# REGENIX_Battery_Protection.net
KiCad netlist of a schematic drawn in Altium Designer
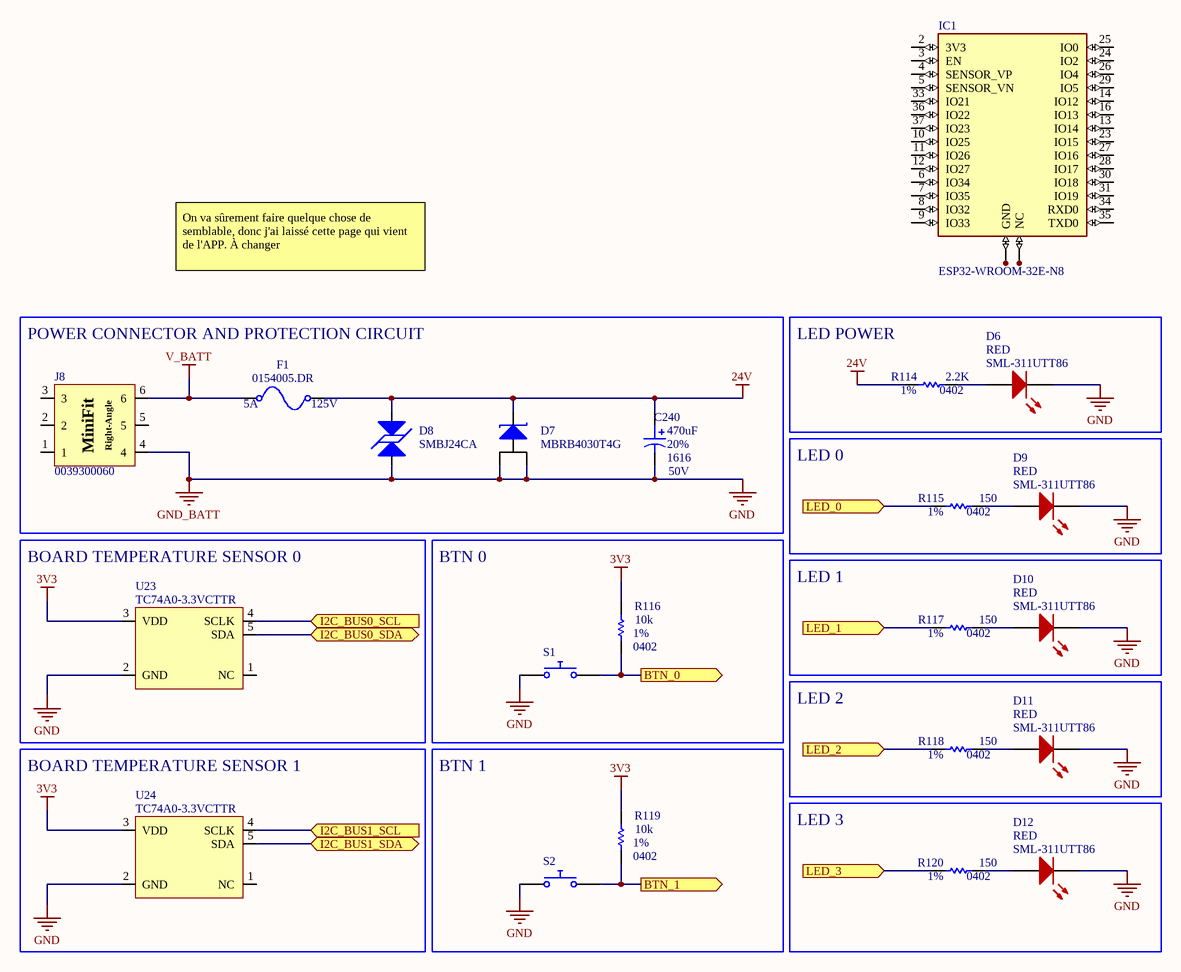
[diagram p0: REGENIX_Battery_Protection.SchDoc]

(export (version "E")
  (design (tool "Eeschema 10.0.6"))
  (components
    (comp (ref "C240")
      (value "470uF")
      (footprint "CAP_ALU_1616_vishay")
      (description "CAP - ALU 470uF 20% 50V - 1616")
      (fields
        (field (name "MFG") "Vishay Dale")
        (field (name "MFG PART NUMBER") "MAL214699108E3")
        (field (name "VOLTAGE") "50V")
        (field (name "PACKAGE") "1616")
        (field (name "PRECISION") "20%")
        (field (name "CREATEDBY") "Jonathan Bouchard")
      )
      (libsource (lib "S7CAS_LIB2023") (part "CAP_ALU_MAL214699108E3"))
    )
    (comp (ref "D6")
      (value "SML-311UTT86")
      (footprint "LED_0603")
      (description "LED - 620nM RED 2mA - 0603")
      (fields
        (field (name "VOLTAGE") "1.8V")
        (field (name "MFG") "ROHM Semiconductor")
        (field (name "ALTIUM_VALUE") "RED")
        (field (name "CREATEDBY") "Jonathan Bouchard")
      )
      (libsource (lib "S7CAS_LIB2023") (part "LED_SML-311UTT86"))
    )
    (comp (ref "D7")
      (value "MBRB4030T4G")
      (footprint "DIO_SCHOTTKY_MBRB4030T4G")
      (description "DIO - 30V MAX 40 A - TO-263-3")
      (fields
        (field (name "CREATEDBY/DATE") "Arnaud Samson - 06/07/18")
        (field (name "VERIFIEDBY") "Jonathan Bouchard 2018-07-12")
      )
      (libsource (lib "S7CAS_LIB2023") (part "DIO_SCHOTTKY_MBRB4030T4G"))
    )
    (comp (ref "D8")
      (value "SMBJ24CA")
      (footprint "TVS_PWR_SMBJ36CA")
      (description "TVS - 24V 26.7V 600W - DO214AA")
      (fields
        (field (name "CREATEDBY/DATE") "Arnaud Samson - 06/07/18")
        (field (name "VERIFIEDBY") "Jonathan Bouchard - 2018-07-13")
      )
      (libsource (lib "S7CAS_LIB2023") (part "TVS_PWR_SMBJ24CA"))
    )
    (comp (ref "D9")
      (value "SML-311UTT86")
      (footprint "LED_0603")
      (description "LED - 620nM RED 2mA - 0603")
      (fields
        (field (name "VOLTAGE") "1.8V")
        (field (name "MFG") "ROHM Semiconductor")
        (field (name "ALTIUM_VALUE") "RED")
        (field (name "CREATEDBY") "Jonathan Bouchard")
      )
      (libsource (lib "S7CAS_LIB2023") (part "LED_SML-311UTT86"))
    )
    (comp (ref "D10")
      (value "SML-311UTT86")
      (footprint "LED_0603")
      (description "LED - 620nM RED 2mA - 0603")
      (fields
        (field (name "VOLTAGE") "1.8V")
        (field (name "MFG") "ROHM Semiconductor")
        (field (name "ALTIUM_VALUE") "RED")
        (field (name "CREATEDBY") "Jonathan Bouchard")
      )
      (libsource (lib "S7CAS_LIB2023") (part "LED_SML-311UTT86"))
    )
    (comp (ref "D11")
      (value "SML-311UTT86")
      (footprint "LED_0603")
      (description "LED - 620nM RED 2mA - 0603")
      (fields
        (field (name "VOLTAGE") "1.8V")
        (field (name "MFG") "ROHM Semiconductor")
        (field (name "ALTIUM_VALUE") "RED")
        (field (name "CREATEDBY") "Jonathan Bouchard")
      )
      (libsource (lib "S7CAS_LIB2023") (part "LED_SML-311UTT86"))
    )
    (comp (ref "D12")
      (value "SML-311UTT86")
      (footprint "LED_0603")
      (description "LED - 620nM RED 2mA - 0603")
      (fields
        (field (name "VOLTAGE") "1.8V")
        (field (name "MFG") "ROHM Semiconductor")
        (field (name "ALTIUM_VALUE") "RED")
        (field (name "CREATEDBY") "Jonathan Bouchard")
      )
      (libsource (lib "S7CAS_LIB2023") (part "LED_SML-311UTT86"))
    )
    (comp (ref "F1")
      (value "0154005.DR")
      (footprint "FUS_0154XXX.DR")
      (description "FUS - 5 A 125 VAC/VDC - 2-SMD")
      (fields
        (field (name "VOLTAGE RATING") "125V")
        (field (name "CURRENT RATING") "5A")
        (field (name "CREATEDBY/DATE") "Arnaud Samson - 06/07/18")
        (field (name "VERIFIEDBY") "Jonathan Bouchard 2018-07-16")
      )
      (libsource (lib "S7CAS_LIB2023") (part "FUS_0154005.DR"))
    )
    (comp (ref "IC1")
      (value "ESP32-WROOM-32E-N8")
      (footprint "ESP32WROOM32EN8")
      (fields (field (name "MF") "Espressif Systems"))
      (libsource (lib "ESP32-WROOM-32E-N8") (part "ESP32-WROOM-32E-N8"))
    )
    (comp (ref "J8")
      (value "0039300060")
      (footprint "CON_MINIFIT_0039300060")
      (description "CON - Mini-Fit Through Hole, Right Angle 6 position")
      (fields
        (field (name "CREATEDBY/DATE") "Joel Lemay 2018-06-21")
        (field (name "VERIFIEDBY") "Caroline Paulin - 10 sept 2018")
      )
      (libsource (lib "S7CAS_LIB2023") (part "CON_MINIFIT_0039300060"))
    )
    (comp (ref "R114")
      (value "2.2K")
      (footprint "RES_0402")
      (description "RES - 0402")
      (fields
        (field (name "VOLTAGE") "50V")
        (field (name "POWER") "1/16W")
        (field (name "PACKAGE") "0402")
        (field (name "PRECISION") "1%")
        (field (name "CREATEDBY") "Jonathan Bouchard")
      )
      (libsource (lib "S7CAS_LIB2023") (part "RES - 0402"))
    )
    (comp (ref "R115")
      (value "150")
      (footprint "RES_0402")
      (description "RES - 0402")
      (fields
        (field (name "VOLTAGE") "50V")
        (field (name "POWER") "1/16W")
        (field (name "PACKAGE") "0402")
        (field (name "PRECISION") "1%")
        (field (name "CREATEDBY") "Jonathan Bouchard")
      )
      (libsource (lib "S7CAS_LIB2023") (part "RES - 0402"))
    )
    (comp (ref "R116")
      (value "10k")
      (footprint "RES_0402")
      (description "RES - 0402")
      (fields
        (field (name "VOLTAGE") "50V")
        (field (name "POWER") "1/16W")
        (field (name "PACKAGE") "0402")
        (field (name "PRECISION") "1%")
        (field (name "CREATEDBY") "Jonathan Bouchard")
      )
      (libsource (lib "S7CAS_LIB2023") (part "RES - 0402"))
    )
    (comp (ref "R117")
      (value "150")
      (footprint "RES_0402")
      (description "RES - 0402")
      (fields
        (field (name "VOLTAGE") "50V")
        (field (name "POWER") "1/16W")
        (field (name "PACKAGE") "0402")
        (field (name "PRECISION") "1%")
        (field (name "CREATEDBY") "Jonathan Bouchard")
      )
      (libsource (lib "S7CAS_LIB2023") (part "RES - 0402"))
    )
    (comp (ref "R118")
      (value "150")
      (footprint "RES_0402")
      (description "RES - 0402")
      (fields
        (field (name "VOLTAGE") "50V")
        (field (name "POWER") "1/16W")
        (field (name "PACKAGE") "0402")
        (field (name "PRECISION") "1%")
        (field (name "CREATEDBY") "Jonathan Bouchard")
      )
      (libsource (lib "S7CAS_LIB2023") (part "RES - 0402"))
    )
    (comp (ref "R119")
      (value "10k")
      (footprint "RES_0402")
      (description "RES - 0402")
      (fields
        (field (name "VOLTAGE") "50V")
        (field (name "POWER") "1/16W")
        (field (name "PACKAGE") "0402")
        (field (name "PRECISION") "1%")
        (field (name "CREATEDBY") "Jonathan Bouchard")
      )
      (libsource (lib "S7CAS_LIB2023") (part "RES - 0402"))
    )
    (comp (ref "R120")
      (value "150")
      (footprint "RES_0402")
      (description "RES - 0402")
      (fields
        (field (name "VOLTAGE") "50V")
        (field (name "POWER") "1/16W")
        (field (name "PACKAGE") "0402")
        (field (name "PRECISION") "1%")
        (field (name "CREATEDBY") "Jonathan Bouchard")
      )
      (libsource (lib "S7CAS_LIB2023") (part "RES - 0402"))
    )
    (comp (ref "S1")
      (value "Push Button Normally Opened")
      (libsource (lib "Simulation Generic Components") (part "Push Button NO"))
    )
    (comp (ref "S2")
      (value "Push Button Normally Opened")
      (libsource (lib "Simulation Generic Components") (part "Push Button NO"))
    )
    (comp (ref "U23")
      (value "TC74A0-3.3VCTTR")
      (footprint "SEN_TEMP_TC74A0-3.3VCTTR")
      (description "SENS - TEMPERATURE SENSOR I2C/SMBUS - SOT23-5")
      (fields
        (field (name "VOLTAGE") "2.7 V ~ 5.5 V")
        (field (name "MFG") "Microchip")
        (field (name "CREATEDBY") "Jonathan Bouchard")
      )
      (libsource (lib "S7CAS_LIB2023") (part "SENS_TEMP_TC74A0-3.3VCTTR"))
    )
    (comp (ref "U24")
      (value "TC74A0-3.3VCTTR")
      (footprint "SEN_TEMP_TC74A0-3.3VCTTR")
      (description "SENS - TEMPERATURE SENSOR I2C/SMBUS - SOT23-5")
      (fields
        (field (name "VOLTAGE") "2.7 V ~ 5.5 V")
        (field (name "MFG") "Microchip")
        (field (name "CREATEDBY") "Jonathan Bouchard")
      )
      (libsource (lib "S7CAS_LIB2023") (part "SENS_TEMP_TC74A0-3.3VCTTR"))
    )
  )
  (nets
    (net (code "1") (name "/BTN_0") (class "Default")
      (node (ref "R116") (pin "1") (pinfunction "1_1") (pintype "passive"))
      (node (ref "S1") (pin "2") (pinfunction "2_2") (pintype "passive"))
    )
    (net (code "2") (name "/BTN_1") (class "Default")
      (node (ref "R119") (pin "1") (pinfunction "1_1") (pintype "passive"))
      (node (ref "S2") (pin "2") (pinfunction "2_2") (pintype "passive"))
    )
    (net (code "3") (name "/I2C_BUS0_SCL") (class "Default")
      (node (ref "U23") (pin "4") (pinfunction "SCLK_4") (pintype "passive"))
    )
    (net (code "4") (name "/I2C_BUS0_SDA") (class "Default")
      (node (ref "U23") (pin "5") (pinfunction "SDA_5") (pintype "passive"))
    )
    (net (code "5") (name "/I2C_BUS1_SCL") (class "Default")
      (node (ref "U24") (pin "4") (pinfunction "SCLK_4") (pintype "passive"))
    )
    (net (code "6") (name "/I2C_BUS1_SDA") (class "Default")
      (node (ref "U24") (pin "5") (pinfunction "SDA_5") (pintype "passive"))
    )
    (net (code "7") (name "/LED_0") (class "Default")
      (node (ref "R115") (pin "2") (pinfunction "2_2") (pintype "passive"))
    )
    (net (code "8") (name "/LED_1") (class "Default")
      (node (ref "R117") (pin "2") (pinfunction "2_2") (pintype "passive"))
    )
    (net (code "9") (name "/LED_2") (class "Default")
      (node (ref "R118") (pin "2") (pinfunction "2_2") (pintype "passive"))
    )
    (net (code "10") (name "/LED_3") (class "Default")
      (node (ref "R120") (pin "2") (pinfunction "2_2") (pintype "passive"))
    )
    (net (code "11") (name "3V3") (class "Default")
      (node (ref "R116") (pin "2") (pinfunction "2_2") (pintype "passive"))
      (node (ref "R119") (pin "2") (pinfunction "2_2") (pintype "passive"))
      (node (ref "U23") (pin "3") (pinfunction "VDD_3") (pintype "passive"))
      (node (ref "U24") (pin "3") (pinfunction "VDD_3") (pintype "passive"))
    )
    (net (code "12") (name "24V") (class "Default")
      (node (ref "C240") (pin "1") (pinfunction "1_1") (pintype "passive"))
      (node (ref "D7") (pin "4") (pinfunction "4_4") (pintype "passive"))
      (node (ref "D8") (pin "1") (pinfunction "1_1") (pintype "passive"))
      (node (ref "F1") (pin "2") (pinfunction "2_2") (pintype "passive"))
      (node (ref "R114") (pin "2") (pinfunction "2_2") (pintype "passive"))
    )
    (net (code "13") (name "GND") (class "Default")
      (node (ref "C240") (pin "2") (pinfunction "2_2") (pintype "passive"))
      (node (ref "D10") (pin "K") (pinfunction "K_K") (pintype "passive"))
      (node (ref "D11") (pin "K") (pinfunction "K_K") (pintype "passive"))
      (node (ref "D12") (pin "K") (pinfunction "K_K") (pintype "passive"))
      (node (ref "D6") (pin "K") (pinfunction "K_K") (pintype "passive"))
      (node (ref "D7") (pin "1") (pinfunction "A_1") (pintype "passive"))
      (node (ref "D7") (pin "3") (pinfunction "3_3") (pintype "passive"))
      (node (ref "D8") (pin "2") (pinfunction "2_2") (pintype "passive"))
      (node (ref "D9") (pin "K") (pinfunction "K_K") (pintype "passive"))
      (node (ref "J8") (pin "4") (pinfunction "4_4") (pintype "passive"))
      (node (ref "S1") (pin "1") (pinfunction "1_1") (pintype "passive"))
      (node (ref "S2") (pin "1") (pinfunction "1_1") (pintype "passive"))
      (node (ref "U23") (pin "2") (pinfunction "GND_2") (pintype "passive"))
      (node (ref "U24") (pin "2") (pinfunction "GND_2") (pintype "passive"))
    )
    (net (code "14") (name "Net-(D6-PadA)") (class "Default")
      (node (ref "D6") (pin "A") (pinfunction "A_A") (pintype "passive"))
      (node (ref "R114") (pin "1") (pinfunction "1_1") (pintype "passive"))
    )
    (net (code "15") (name "Net-(D9-PadA)") (class "Default")
      (node (ref "D9") (pin "A") (pinfunction "A_A") (pintype "passive"))
      (node (ref "R115") (pin "1") (pinfunction "1_1") (pintype "passive"))
    )
    (net (code "16") (name "Net-(D10-PadA)") (class "Default")
      (node (ref "D10") (pin "A") (pinfunction "A_A") (pintype "passive"))
      (node (ref "R117") (pin "1") (pinfunction "1_1") (pintype "passive"))
    )
    (net (code "17") (name "Net-(D11-PadA)") (class "Default")
      (node (ref "D11") (pin "A") (pinfunction "A_A") (pintype "passive"))
      (node (ref "R118") (pin "1") (pinfunction "1_1") (pintype "passive"))
    )
    (net (code "18") (name "Net-(D12-PadA)") (class "Default")
      (node (ref "D12") (pin "A") (pinfunction "A_A") (pintype "passive"))
      (node (ref "R120") (pin "1") (pinfunction "1_1") (pintype "passive"))
    )
    (net (code "19") (name "Net-(IC1-GND-Pad1)") (class "Default")
      (node (ref "IC1") (pin "1") (pinfunction "GND_1") (pintype "bidirectional"))
      (node (ref "IC1") (pin "15") (pinfunction "GND_15") (pintype "bidirectional"))
      (node (ref "IC1") (pin "38") (pinfunction "GND_38") (pintype "bidirectional"))
      (node (ref "IC1") (pin "39") (pinfunction "GND_39") (pintype "bidirectional"))
      (node (ref "IC1") (pin "40") (pinfunction "GND_40") (pintype "bidirectional"))
      (node (ref "IC1") (pin "41") (pinfunction "GND_41") (pintype "bidirectional"))
      (node (ref "IC1") (pin "42") (pinfunction "GND_42") (pintype "bidirectional"))
      (node (ref "IC1") (pin "43") (pinfunction "GND_43") (pintype "bidirectional"))
      (node (ref "IC1") (pin "44") (pinfunction "GND_44") (pintype "bidirectional"))
      (node (ref "IC1") (pin "45") (pinfunction "GND_45") (pintype "bidirectional"))
      (node (ref "IC1") (pin "46") (pinfunction "GND_46") (pintype "bidirectional"))
      (node (ref "IC1") (pin "47") (pinfunction "GND_47") (pintype "bidirectional"))
    )
    (net (code "20") (name "Net-(IC1-NC-Pad17)") (class "Default")
      (node (ref "IC1") (pin "17") (pinfunction "NC_17") (pintype "bidirectional"))
      (node (ref "IC1") (pin "18") (pinfunction "NC_18") (pintype "bidirectional"))
      (node (ref "IC1") (pin "19") (pinfunction "NC_19") (pintype "bidirectional"))
      (node (ref "IC1") (pin "20") (pinfunction "NC_20") (pintype "bidirectional"))
      (node (ref "IC1") (pin "21") (pinfunction "NC_21") (pintype "bidirectional"))
      (node (ref "IC1") (pin "22") (pinfunction "NC_22") (pintype "bidirectional"))
      (node (ref "IC1") (pin "32") (pinfunction "NC_32") (pintype "bidirectional"))
    )
    (net (code "21") (name "V_BATT") (class "Default")
      (node (ref "F1") (pin "1") (pinfunction "1_1") (pintype "passive"))
      (node (ref "J8") (pin "6") (pinfunction "6_6") (pintype "passive"))
    )
    (net (code "22") (name "unconnected-(IC1-3V3-Pad2)") (class "Default")
      (node (ref "IC1") (pin "2") (pinfunction "3V3_2") (pintype "bidirectional"))
    )
    (net (code "23") (name "unconnected-(IC1-EN-Pad3)") (class "Default")
      (node (ref "IC1") (pin "3") (pinfunction "EN_3") (pintype "bidirectional"))
    )
    (net (code "24") (name "unconnected-(IC1-IO0-Pad25)") (class "Default")
      (node (ref "IC1") (pin "25") (pinfunction "IO0_25") (pintype "bidirectional"))
    )
    (net (code "25") (name "unconnected-(IC1-IO2-Pad24)") (class "Default")
      (node (ref "IC1") (pin "24") (pinfunction "IO2_24") (pintype "bidirectional"))
    )
    (net (code "26") (name "unconnected-(IC1-IO4-Pad26)") (class "Default")
      (node (ref "IC1") (pin "26") (pinfunction "IO4_26") (pintype "bidirectional"))
    )
    (net (code "27") (name "unconnected-(IC1-IO5-Pad29)") (class "Default")
      (node (ref "IC1") (pin "29") (pinfunction "IO5_29") (pintype "bidirectional"))
    )
    (net (code "28") (name "unconnected-(IC1-IO12-Pad14)") (class "Default")
      (node (ref "IC1") (pin "14") (pinfunction "IO12_14") (pintype "bidirectional"))
    )
    (net (code "29") (name "unconnected-(IC1-IO13-Pad16)") (class "Default")
      (node (ref "IC1") (pin "16") (pinfunction "IO13_16") (pintype "bidirectional"))
    )
    (net (code "30") (name "unconnected-(IC1-IO14-Pad13)") (class "Default")
      (node (ref "IC1") (pin "13") (pinfunction "IO14_13") (pintype "bidirectional"))
    )
    (net (code "31") (name "unconnected-(IC1-IO15-Pad23)") (class "Default")
      (node (ref "IC1") (pin "23") (pinfunction "IO15_23") (pintype "bidirectional"))
    )
    (net (code "32") (name "unconnected-(IC1-IO16-Pad27)") (class "Default")
      (node (ref "IC1") (pin "27") (pinfunction "IO16_27") (pintype "bidirectional"))
    )
    (net (code "33") (name "unconnected-(IC1-IO17-Pad28)") (class "Default")
      (node (ref "IC1") (pin "28") (pinfunction "IO17_28") (pintype "bidirectional"))
    )
    (net (code "34") (name "unconnected-(IC1-IO18-Pad30)") (class "Default")
      (node (ref "IC1") (pin "30") (pinfunction "IO18_30") (pintype "bidirectional"))
    )
    (net (code "35") (name "unconnected-(IC1-IO19-Pad31)") (class "Default")
      (node (ref "IC1") (pin "31") (pinfunction "IO19_31") (pintype "bidirectional"))
    )
    (net (code "36") (name "unconnected-(IC1-IO21-Pad33)") (class "Default")
      (node (ref "IC1") (pin "33") (pinfunction "IO21_33") (pintype "bidirectional"))
    )
    (net (code "37") (name "unconnected-(IC1-IO22-Pad36)") (class "Default")
      (node (ref "IC1") (pin "36") (pinfunction "IO22_36") (pintype "bidirectional"))
    )
    (net (code "38") (name "unconnected-(IC1-IO23-Pad37)") (class "Default")
      (node (ref "IC1") (pin "37") (pinfunction "IO23_37") (pintype "bidirectional"))
    )
    (net (code "39") (name "unconnected-(IC1-IO25-Pad10)") (class "Default")
      (node (ref "IC1") (pin "10") (pinfunction "IO25_10") (pintype "bidirectional"))
    )
    (net (code "40") (name "unconnected-(IC1-IO26-Pad11)") (class "Default")
      (node (ref "IC1") (pin "11") (pinfunction "IO26_11") (pintype "bidirectional"))
    )
    (net (code "41") (name "unconnected-(IC1-IO27-Pad12)") (class "Default")
      (node (ref "IC1") (pin "12") (pinfunction "IO27_12") (pintype "bidirectional"))
    )
    (net (code "42") (name "unconnected-(IC1-IO32-Pad8)") (class "Default")
      (node (ref "IC1") (pin "8") (pinfunction "IO32_8") (pintype "bidirectional"))
    )
    (net (code "43") (name "unconnected-(IC1-IO33-Pad9)") (class "Default")
      (node (ref "IC1") (pin "9") (pinfunction "IO33_9") (pintype "bidirectional"))
    )
    (net (code "44") (name "unconnected-(IC1-IO34-Pad6)") (class "Default")
      (node (ref "IC1") (pin "6") (pinfunction "IO34_6") (pintype "bidirectional"))
    )
    (net (code "45") (name "unconnected-(IC1-IO35-Pad7)") (class "Default")
      (node (ref "IC1") (pin "7") (pinfunction "IO35_7") (pintype "bidirectional"))
    )
    (net (code "46") (name "unconnected-(IC1-RXD0-Pad34)") (class "Default")
      (node (ref "IC1") (pin "34") (pinfunction "RXD0_34") (pintype "bidirectional"))
    )
    (net (code "47") (name "unconnected-(IC1-SENSOR_VN-Pad5)") (class "Default")
      (node (ref "IC1") (pin "5") (pinfunction "SENSOR_VN_5") (pintype "bidirectional"))
    )
    (net (code "48") (name "unconnected-(IC1-SENSOR_VP-Pad4)") (class "Default")
      (node (ref "IC1") (pin "4") (pinfunction "SENSOR_VP_4") (pintype "bidirectional"))
    )
    (net (code "49") (name "unconnected-(IC1-TXD0-Pad35)") (class "Default")
      (node (ref "IC1") (pin "35") (pinfunction "TXD0_35") (pintype "bidirectional"))
    )
    (net (code "50") (name "unconnected-(J8-Pad1)") (class "Default")
      (node (ref "J8") (pin "1") (pinfunction "1_1") (pintype "passive"))
    )
    (net (code "51") (name "unconnected-(J8-Pad2)") (class "Default")
      (node (ref "J8") (pin "2") (pinfunction "2_2") (pintype "passive"))
    )
    (net (code "52") (name "unconnected-(J8-Pad3)") (class "Default")
      (node (ref "J8") (pin "3") (pinfunction "3_3") (pintype "passive"))
    )
    (net (code "53") (name "unconnected-(J8-Pad5)") (class "Default")
      (node (ref "J8") (pin "5") (pinfunction "5_5") (pintype "passive"))
    )
    (net (code "54") (name "unconnected-(U23-NC-Pad1)") (class "Default")
      (node (ref "U23") (pin "1") (pinfunction "NC_1") (pintype "passive"))
    )
    (net (code "55") (name "unconnected-(U24-NC-Pad1)") (class "Default")
      (node (ref "U24") (pin "1") (pinfunction "NC_1") (pintype "passive"))
    )
  )
)
